# 3_-LEDBoard.net
KiCad netlist of a schematic drawn in Altium Designer
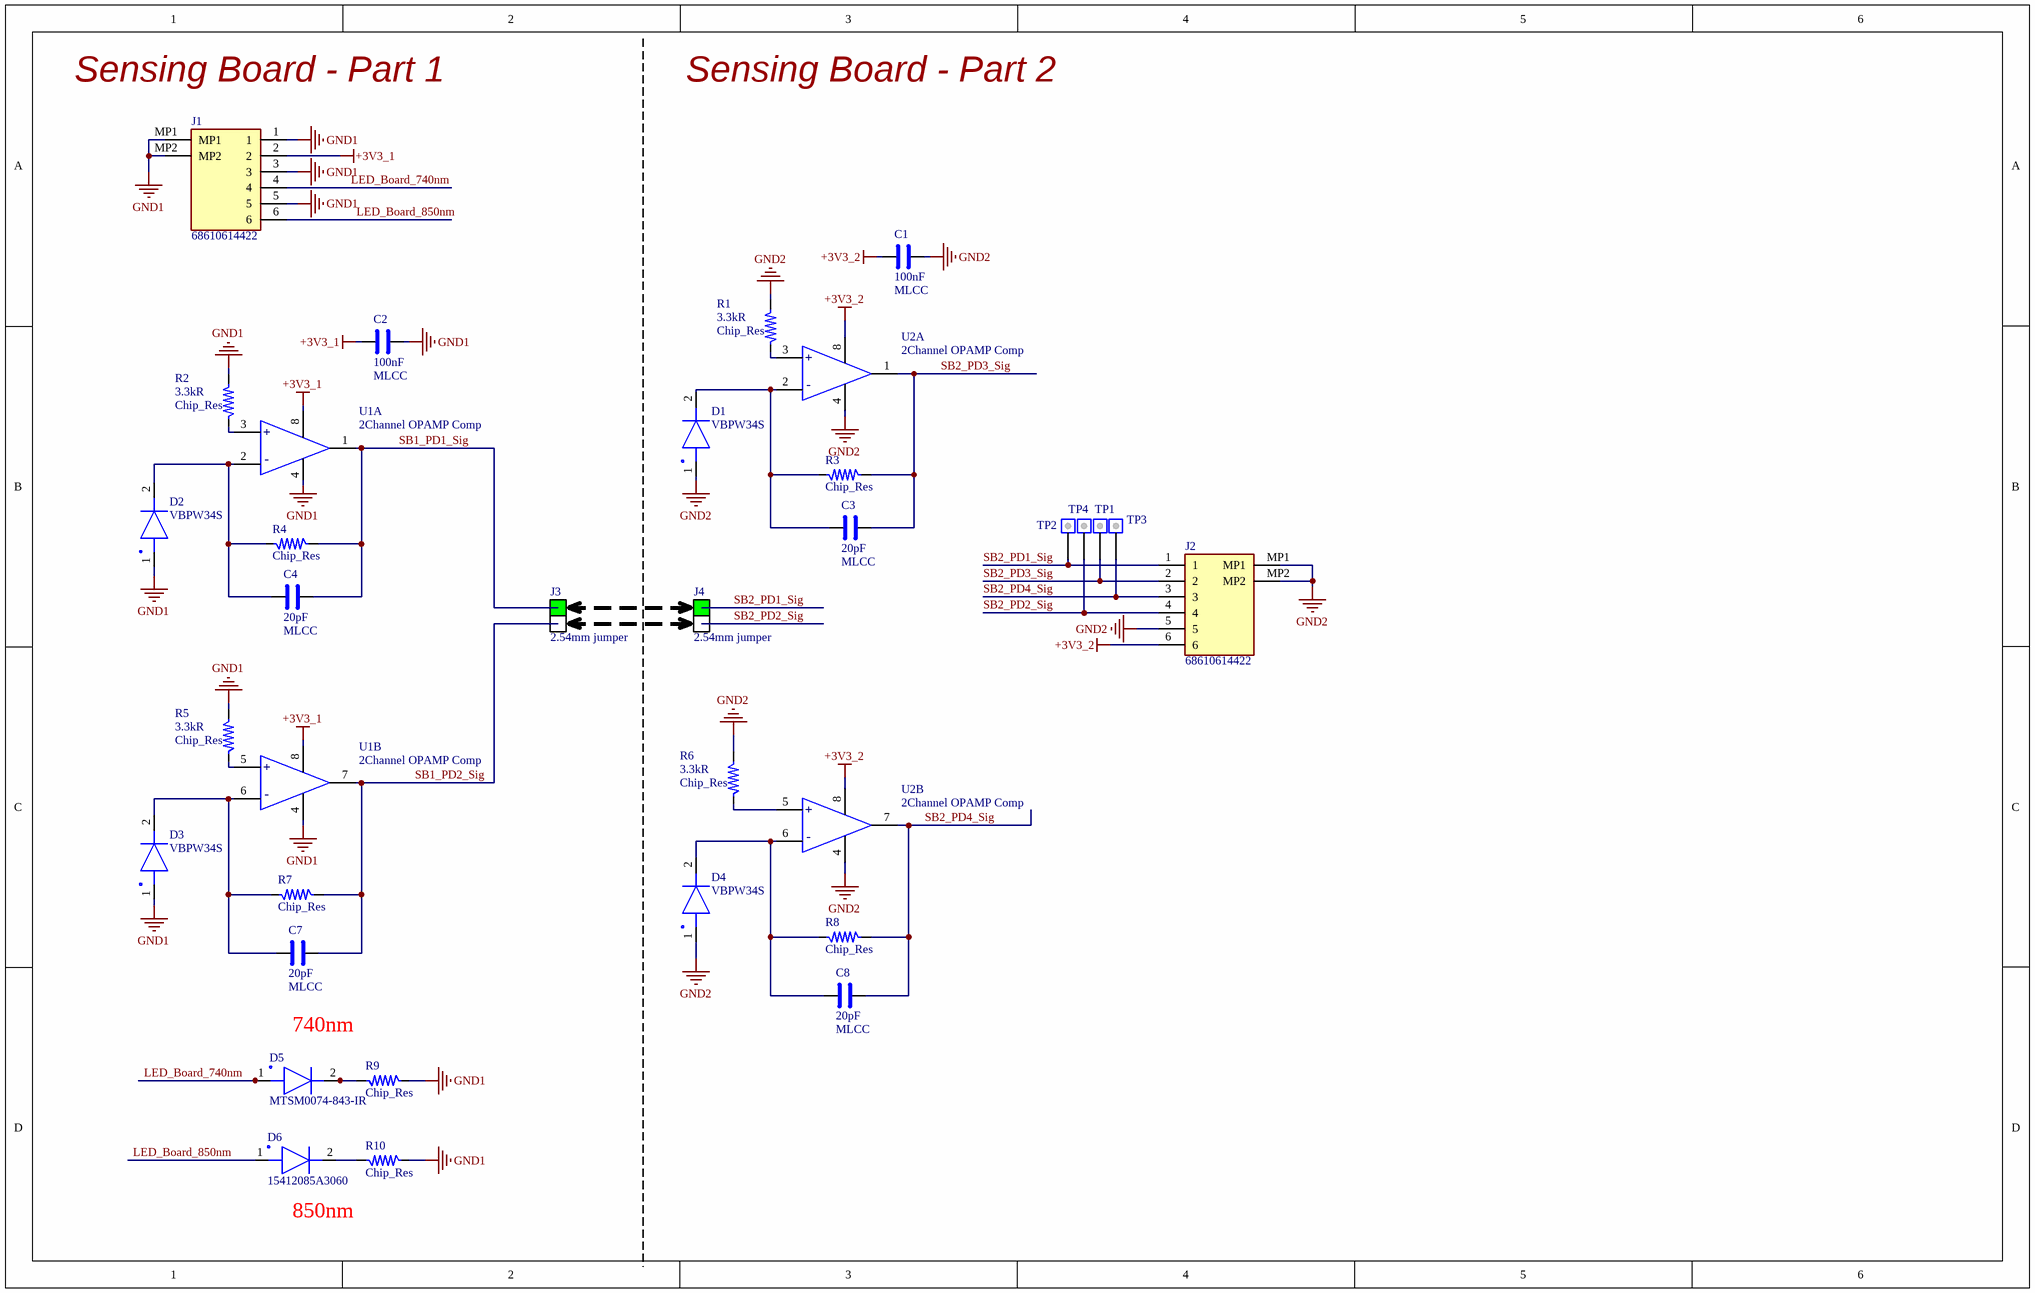
[diagram p0: [3]-LEDBoard.SchDoc]

(export (version "E")
  (design (tool "Eeschema 10.0.6"))
  (components
    (comp (ref "C1")
      (value "MLCC")
      (footprint "CAPC1005X06L")
      (description "Multilayer Ceramic Capacitor, 0.1 uF, 25 V, ± 10%, X7R, 0402 [1005 Metric]")
      (fields
        (field (name "PART NUMBER") "CC0402KRX7R8BB104")
        (field (name "ALTIUM_VALUE") "100nF")
        (field (name "MANUFACTURER") "Yageo")
      )
      (libsource (lib "Capacitors") (part "MLCC"))
    )
    (comp (ref "C2")
      (value "MLCC")
      (footprint "CAPC1005X06L")
      (description "Multilayer Ceramic Capacitor, 0.1 uF, 25 V, ± 10%, X7R, 0402 [1005 Metric]")
      (fields
        (field (name "PART NUMBER") "CC0402KRX7R8BB104")
        (field (name "ALTIUM_VALUE") "100nF")
        (field (name "MANUFACTURER") "Yageo")
      )
      (libsource (lib "Capacitors") (part "MLCC"))
    )
    (comp (ref "C3")
      (value "MLCC")
      (footprint "CAPC1608X09M")
      (description "Multilayer Ceramic Capacitor, 20 pF, 50 V, ± 5%, C0G (NP0), 0603 [1608 Metric]")
      (fields
        (field (name "PART NUMBER") "CC0603JRNPO9BN200")
        (field (name "ALTIUM_VALUE") "20pF")
        (field (name "MANUFACTURER") "Yageo")
      )
      (libsource (lib "Capacitors") (part "MLCC"))
    )
    (comp (ref "C4")
      (value "MLCC")
      (footprint "CAPC1608X09M")
      (description "Multilayer Ceramic Capacitor, 20 pF, 50 V, ± 5%, C0G (NP0), 0603 [1608 Metric]")
      (fields
        (field (name "PART NUMBER") "CC0603JRNPO9BN200")
        (field (name "ALTIUM_VALUE") "20pF")
        (field (name "MANUFACTURER") "Yageo")
      )
      (libsource (lib "Capacitors") (part "MLCC"))
    )
    (comp (ref "C7")
      (value "MLCC")
      (footprint "CAPC1608X09M")
      (description "Multilayer Ceramic Capacitor, 20 pF, 50 V, ± 5%, C0G (NP0), 0603 [1608 Metric]")
      (fields
        (field (name "PART NUMBER") "CC0603JRNPO9BN200")
        (field (name "ALTIUM_VALUE") "20pF")
        (field (name "MANUFACTURER") "Yageo")
      )
      (libsource (lib "Capacitors") (part "MLCC"))
    )
    (comp (ref "C8")
      (value "MLCC")
      (footprint "CAPC1608X09M")
      (description "Multilayer Ceramic Capacitor, 20 pF, 50 V, ± 5%, C0G (NP0), 0603 [1608 Metric]")
      (fields
        (field (name "PART NUMBER") "CC0603JRNPO9BN200")
        (field (name "ALTIUM_VALUE") "20pF")
        (field (name "MANUFACTURER") "Yageo")
      )
      (libsource (lib "Capacitors") (part "MLCC"))
    )
    (comp (ref "D1")
      (value "VBPW34S")
      (footprint "VBPW34S")
      (description "Photodiode 940nm 100ns 130° 2-SMD, Gull Wing")
      (fields (field (name "MANUFACTURER") "Vishay"))
      (libsource (lib "Optic") (part "VBPW34S"))
    )
    (comp (ref "D2")
      (value "VBPW34S")
      (footprint "VBPW34S")
      (description "Photodiode 940nm 100ns 130° 2-SMD, Gull Wing")
      (fields (field (name "MANUFACTURER") "Vishay"))
      (libsource (lib "Optic") (part "VBPW34S"))
    )
    (comp (ref "D3")
      (value "VBPW34S")
      (footprint "VBPW34S")
      (description "Photodiode 940nm 100ns 130° 2-SMD, Gull Wing")
      (fields (field (name "MANUFACTURER") "Vishay"))
      (libsource (lib "Optic") (part "VBPW34S"))
    )
    (comp (ref "D4")
      (value "VBPW34S")
      (footprint "VBPW34S")
      (description "Photodiode 940nm 100ns 130° 2-SMD, Gull Wing")
      (fields (field (name "MANUFACTURER") "Vishay"))
      (libsource (lib "Optic") (part "VBPW34S"))
    )
    (comp (ref "D5")
      (value "MTSM0074-843-IR")
      (footprint "MTSM0074-843-IR")
      (description "Infrared (IR) Emitter 740nm 1.7V 30mA 3.2mW/sr @ 30mA 1206 (3216 Metric)")
      (fields (field (name "MANUFACTURER") "Marktech Optoelectronics"))
      (libsource (lib "Optic") (part "MTSM0074-843-IR"))
    )
    (comp (ref "D6")
      (value "15412085A3060")
      (footprint "15412085A3060")
      (description "Infrared (IR) Emitter 850nm 1.4V 15mW/sr @ 20mA 30° 1206 (3216 Metric)")
      (fields (field (name "MANUFACTURER") "Wurth Elektronik"))
      (libsource (lib "Optic") (part "15412085A3060"))
    )
    (comp (ref "J1")
      (value "68610614422")
      (footprint "68610614422")
      (description "6 Position FPC Connector Contacts, Bottom 0.039\" (1.00mm) Surface Mount, Right Angle")
      (fields (field (name "MANUFACTURER") "Würth Elektronik"))
      (libsource (lib "Connector") (part "68610614422"))
    )
    (comp (ref "J2")
      (value "68610614422")
      (footprint "68610614422")
      (description "6 Position FPC Connector Contacts, Bottom 0.039\" (1.00mm) Surface Mount, Right Angle")
      (fields (field (name "MANUFACTURER") "Würth Elektronik"))
      (libsource (lib "") (part "68610614422_1"))
    )
    (comp (ref "J3")
      (value "2.54mm jumper")
      (footprint "FP_Jumper_2x2_54mm")
      (description "2x2.54mm conventional header as jumper")
      (fields (field (name "PART NUMBER") "Header2x1"))
      (libsource (lib "Connector") (part "Header2x1"))
    )
    (comp (ref "J4")
      (value "2.54mm jumper")
      (footprint "FP_Jumper_2x2_54mm")
      (description "2x2.54mm conventional header as jumper")
      (fields (field (name "PART NUMBER") "Header2x1"))
      (libsource (lib "Connector") (part "Header2x1"))
    )
    (comp (ref "R1")
      (value "Chip_Res")
      (footprint "RESC1005X04M")
      (description "SMD Chip Resistor, 3.3 kOhm, ± 5%, 63 mW, 0402 [1005 Metric], Thick Film, General Purpose")
      (fields
        (field (name "PART NUMBER") "RC0402JR-073K3L")
        (field (name "ALTIUM_VALUE") "3.3kR")
        (field (name "MANUFACTURER") "Yageo")
      )
      (libsource (lib "Resistors") (part "Chip_Res"))
    )
    (comp (ref "R2")
      (value "Chip_Res")
      (footprint "RESC1005X04M")
      (description "SMD Chip Resistor, 3.3 kOhm, ± 5%, 63 mW, 0402 [1005 Metric], Thick Film, General Purpose")
      (fields
        (field (name "PART NUMBER") "RC0402JR-073K3L")
        (field (name "ALTIUM_VALUE") "3.3kR")
        (field (name "MANUFACTURER") "Yageo")
      )
      (libsource (lib "Resistors") (part "Chip_Res"))
    )
    (comp (ref "R3")
      (value "Chip_Res")
      (footprint "RESC1608X06M")
      (description "Res Thick Film 0603 887 Ohm 1% 1/10W ±100ppm/°C Molded SMD SMD Paper T/R")
      (fields (field (name "PART NUMBER") "RC0603FR-07887RL") (field (name "MANUFACTURER") "Yageo"))
      (libsource (lib "Resistors") (part "Chip_Res"))
    )
    (comp (ref "R4")
      (value "Chip_Res")
      (footprint "RESC1608X06M")
      (description "Res Thick Film 0603 887 Ohm 1% 1/10W ±100ppm/°C Molded SMD SMD Paper T/R")
      (fields (field (name "PART NUMBER") "RC0603FR-07887RL") (field (name "MANUFACTURER") "Yageo"))
      (libsource (lib "Resistors") (part "Chip_Res"))
    )
    (comp (ref "R5")
      (value "Chip_Res")
      (footprint "RESC1005X04M")
      (description "SMD Chip Resistor, 3.3 kOhm, ± 5%, 63 mW, 0402 [1005 Metric], Thick Film, General Purpose")
      (fields
        (field (name "PART NUMBER") "RC0402JR-073K3L")
        (field (name "ALTIUM_VALUE") "3.3kR")
        (field (name "MANUFACTURER") "Yageo")
      )
      (libsource (lib "Resistors") (part "Chip_Res"))
    )
    (comp (ref "R6")
      (value "Chip_Res")
      (footprint "RESC1005X04M")
      (description "SMD Chip Resistor, 3.3 kOhm, ± 5%, 63 mW, 0402 [1005 Metric], Thick Film, General Purpose")
      (fields
        (field (name "PART NUMBER") "RC0402JR-073K3L")
        (field (name "ALTIUM_VALUE") "3.3kR")
        (field (name "MANUFACTURER") "Yageo")
      )
      (libsource (lib "Resistors") (part "Chip_Res"))
    )
    (comp (ref "R7")
      (value "Chip_Res")
      (footprint "RESC1608X06M")
      (description "Res Thick Film 0603 887 Ohm 1% 1/10W ±100ppm/°C Molded SMD SMD Paper T/R")
      (fields (field (name "PART NUMBER") "RC0603FR-07887RL") (field (name "MANUFACTURER") "Yageo"))
      (libsource (lib "Resistors") (part "Chip_Res"))
    )
    (comp (ref "R8")
      (value "Chip_Res")
      (footprint "RESC1608X06M")
      (description "Res Thick Film 0603 887 Ohm 1% 1/10W ±100ppm/°C Molded SMD SMD Paper T/R")
      (fields (field (name "PART NUMBER") "RC0603FR-07887RL") (field (name "MANUFACTURER") "Yageo"))
      (libsource (lib "Resistors") (part "Chip_Res"))
    )
    (comp (ref "R9")
      (value "Chip_Res")
      (footprint "RESC1608X06M")
      (description "SMD Chip Resistor, 33 kOhm, ± 1%, 100 mW, 0603 [1608 Metric], Thick Film, General Purpose")
      (fields (field (name "PART NUMBER") "AC0603FR-1333KL") (field (name "MANUFACTURER") "Yageo"))
      (libsource (lib "Resistors") (part "Chip_Res"))
    )
    (comp (ref "R10")
      (value "Chip_Res")
      (footprint "RESC1608X06M")
      (description "SMD Chip Resistor, 33 kOhm, ± 1%, 100 mW, 0603 [1608 Metric], Thick Film, General Purpose")
      (fields (field (name "PART NUMBER") "AC0603FR-1333KL") (field (name "MANUFACTURER") "Yageo"))
      (libsource (lib "Resistors") (part "Chip_Res"))
    )
    (comp (ref "TP1")
      (value "TP")
      (footprint "FP-TP_SMD_Narrow")
      (description "A simple test point")
      (fields (field (name "PART NUMBER") "Test Point"))
      (libsource (lib "Miscellaneous") (part "TP"))
    )
    (comp (ref "TP2")
      (value "TP")
      (footprint "FP-TP_SMD_Narrow")
      (description "A simple test point")
      (fields (field (name "PART NUMBER") "Test Point"))
      (libsource (lib "Miscellaneous") (part "TP"))
    )
    (comp (ref "TP3")
      (value "TP")
      (footprint "FP-TP_SMD_Narrow")
      (description "A simple test point")
      (fields (field (name "PART NUMBER") "Test Point"))
      (libsource (lib "Miscellaneous") (part "TP"))
    )
    (comp (ref "TP4")
      (value "TP")
      (footprint "FP-TP_SMD_Narrow")
      (description "A simple test point")
      (fields (field (name "PART NUMBER") "Test Point"))
      (libsource (lib "Miscellaneous") (part "TP"))
    )
    (comp (ref "U1")
      (value "2Channel OPAMP Comp")
      (footprint "TSOP65P490X110-8L")
      (fields (field (name "PART NUMBER") "OPA2380AIDGKR") (field (name "MANUFACTURER") "Texas Instruments"))
      (libsource (lib "ICs") (part "2Channel OPAMP Comp"))
    )
    (comp (ref "U2")
      (value "2Channel OPAMP Comp")
      (footprint "TSOP65P490X110-8L")
      (fields (field (name "PART NUMBER") "OPA2380AIDGKR") (field (name "MANUFACTURER") "Texas Instruments"))
      (libsource (lib "ICs") (part "2Channel OPAMP Comp"))
    )
  )
  (nets
    (net (code "1") (name "+3V3_1") (class "Default")
      (node (ref "C2") (pin "1") (pinfunction "1_1") (pintype "passive"))
      (node (ref "J1") (pin "2") (pinfunction "2_2") (pintype "passive"))
      (node (ref "U1") (pin "8") (pinfunction "VCC_8") (pintype "power_in"))
    )
    (net (code "2") (name "+3V3_2") (class "Default")
      (node (ref "C1") (pin "1") (pinfunction "1_1") (pintype "passive"))
      (node (ref "J2") (pin "6") (pinfunction "6_6") (pintype "passive"))
      (node (ref "U2") (pin "8") (pinfunction "VCC_8") (pintype "power_in"))
    )
    (net (code "3") (name "/LED_Board_740nm") (class "Default")
      (node (ref "D5") (pin "1") (pinfunction "Anode_1") (pintype "passive"))
      (node (ref "J1") (pin "4") (pinfunction "4_4") (pintype "passive"))
    )
    (net (code "4") (name "/LED_Board_850nm") (class "Default")
      (node (ref "D6") (pin "1") (pinfunction "Anode_1") (pintype "passive"))
      (node (ref "J1") (pin "6") (pinfunction "6_6") (pintype "passive"))
    )
    (net (code "5") (name "/SB1_PD1_Sig") (class "Default")
      (node (ref "C4") (pin "2") (pinfunction "2_2") (pintype "passive"))
      (node (ref "J3") (pin "1") (pinfunction "1_1") (pintype "passive"))
      (node (ref "R4") (pin "1") (pinfunction "1_1") (pintype "passive"))
      (node (ref "U1") (pin "1") (pinfunction "1OUT_1") (pintype "passive"))
    )
    (net (code "6") (name "/SB1_PD2_Sig") (class "Default")
      (node (ref "C7") (pin "2") (pinfunction "2_2") (pintype "passive"))
      (node (ref "J3") (pin "2") (pinfunction "2_2") (pintype "passive"))
      (node (ref "R7") (pin "1") (pinfunction "1_1") (pintype "passive"))
      (node (ref "U1") (pin "7") (pinfunction "2OUT_7") (pintype "passive"))
    )
    (net (code "7") (name "/SB2_PD1_Sig") (class "Default")
      (node (ref "J2") (pin "1") (pinfunction "1_1") (pintype "passive"))
      (node (ref "J4") (pin "1") (pinfunction "1_1") (pintype "passive"))
      (node (ref "TP2") (pin "NODE") (pinfunction "NODE_NODE") (pintype "passive"))
    )
    (net (code "8") (name "/SB2_PD2_Sig") (class "Default")
      (node (ref "J2") (pin "4") (pinfunction "4_4") (pintype "passive"))
      (node (ref "J4") (pin "2") (pinfunction "2_2") (pintype "passive"))
      (node (ref "TP4") (pin "NODE") (pinfunction "NODE_NODE") (pintype "passive"))
    )
    (net (code "9") (name "/SB2_PD3_Sig") (class "Default")
      (node (ref "C3") (pin "2") (pinfunction "2_2") (pintype "passive"))
      (node (ref "J2") (pin "2") (pinfunction "2_2") (pintype "passive"))
      (node (ref "R3") (pin "1") (pinfunction "1_1") (pintype "passive"))
      (node (ref "TP1") (pin "NODE") (pinfunction "NODE_NODE") (pintype "passive"))
      (node (ref "U2") (pin "1") (pinfunction "1OUT_1") (pintype "passive"))
    )
    (net (code "10") (name "/SB2_PD4_Sig") (class "Default")
      (node (ref "C8") (pin "2") (pinfunction "2_2") (pintype "passive"))
      (node (ref "J2") (pin "3") (pinfunction "3_3") (pintype "passive"))
      (node (ref "R8") (pin "1") (pinfunction "1_1") (pintype "passive"))
      (node (ref "TP3") (pin "NODE") (pinfunction "NODE_NODE") (pintype "passive"))
      (node (ref "U2") (pin "7") (pinfunction "2OUT_7") (pintype "passive"))
    )
    (net (code "11") (name "GND1") (class "Default")
      (node (ref "C2") (pin "2") (pinfunction "2_2") (pintype "passive"))
      (node (ref "D2") (pin "1") (pinfunction "Anode_1") (pintype "passive"))
      (node (ref "D3") (pin "1") (pinfunction "Anode_1") (pintype "passive"))
      (node (ref "J1") (pin "1") (pinfunction "1_1") (pintype "passive"))
      (node (ref "J1") (pin "3") (pinfunction "3_3") (pintype "passive"))
      (node (ref "J1") (pin "5") (pinfunction "5_5") (pintype "passive"))
      (node (ref "J1") (pin "MP1") (pinfunction "MP1_MP1") (pintype "passive"))
      (node (ref "J1") (pin "MP2") (pinfunction "MP2_MP2") (pintype "passive"))
      (node (ref "R10") (pin "2") (pinfunction "2_2") (pintype "passive"))
      (node (ref "R2") (pin "1") (pinfunction "1_1") (pintype "passive"))
      (node (ref "R5") (pin "1") (pinfunction "1_1") (pintype "passive"))
      (node (ref "R9") (pin "2") (pinfunction "2_2") (pintype "passive"))
      (node (ref "U1") (pin "4") (pinfunction "GND_4") (pintype "power_in"))
    )
    (net (code "12") (name "GND2") (class "Default")
      (node (ref "C1") (pin "2") (pinfunction "2_2") (pintype "passive"))
      (node (ref "D1") (pin "1") (pinfunction "Anode_1") (pintype "passive"))
      (node (ref "D4") (pin "1") (pinfunction "Anode_1") (pintype "passive"))
      (node (ref "J2") (pin "5") (pinfunction "5_5") (pintype "passive"))
      (node (ref "J2") (pin "MP1") (pinfunction "MP1_MP1") (pintype "passive"))
      (node (ref "J2") (pin "MP2") (pinfunction "MP2_MP2") (pintype "passive"))
      (node (ref "R1") (pin "1") (pinfunction "1_1") (pintype "passive"))
      (node (ref "R6") (pin "1") (pinfunction "1_1") (pintype "passive"))
      (node (ref "U2") (pin "4") (pinfunction "GND_4") (pintype "power_in"))
    )
    (net (code "13") (name "Net-(D1-Cathode)") (class "Default")
      (node (ref "C3") (pin "1") (pinfunction "1_1") (pintype "passive"))
      (node (ref "D1") (pin "2") (pinfunction "Cathode_2") (pintype "passive"))
      (node (ref "R3") (pin "2") (pinfunction "2_2") (pintype "passive"))
      (node (ref "U2") (pin "2") (pinfunction "1IN-_2") (pintype "passive"))
    )
    (net (code "14") (name "Net-(D2-Cathode)") (class "Default")
      (node (ref "C4") (pin "1") (pinfunction "1_1") (pintype "passive"))
      (node (ref "D2") (pin "2") (pinfunction "Cathode_2") (pintype "passive"))
      (node (ref "R4") (pin "2") (pinfunction "2_2") (pintype "passive"))
      (node (ref "U1") (pin "2") (pinfunction "1IN-_2") (pintype "passive"))
    )
    (net (code "15") (name "Net-(D3-Cathode)") (class "Default")
      (node (ref "C7") (pin "1") (pinfunction "1_1") (pintype "passive"))
      (node (ref "D3") (pin "2") (pinfunction "Cathode_2") (pintype "passive"))
      (node (ref "R7") (pin "2") (pinfunction "2_2") (pintype "passive"))
      (node (ref "U1") (pin "6") (pinfunction "2IN-_6") (pintype "passive"))
    )
    (net (code "16") (name "Net-(D4-Cathode)") (class "Default")
      (node (ref "C8") (pin "1") (pinfunction "1_1") (pintype "passive"))
      (node (ref "D4") (pin "2") (pinfunction "Cathode_2") (pintype "passive"))
      (node (ref "R8") (pin "2") (pinfunction "2_2") (pintype "passive"))
      (node (ref "U2") (pin "6") (pinfunction "2IN-_6") (pintype "passive"))
    )
    (net (code "17") (name "Net-(D5-Cathode)") (class "Default")
      (node (ref "D5") (pin "2") (pinfunction "Cathode_2") (pintype "passive"))
      (node (ref "R9") (pin "1") (pinfunction "1_1") (pintype "passive"))
    )
    (net (code "18") (name "Net-(D6-Cathode)") (class "Default")
      (node (ref "D6") (pin "2") (pinfunction "Cathode_2") (pintype "passive"))
      (node (ref "R10") (pin "1") (pinfunction "1_1") (pintype "passive"))
    )
    (net (code "19") (name "Net-(U1A-1IN+)") (class "Default")
      (node (ref "R2") (pin "2") (pinfunction "2_2") (pintype "passive"))
      (node (ref "U1") (pin "3") (pinfunction "1IN+_3") (pintype "passive"))
    )
    (net (code "20") (name "Net-(U1B-2IN+)") (class "Default")
      (node (ref "R5") (pin "2") (pinfunction "2_2") (pintype "passive"))
      (node (ref "U1") (pin "5") (pinfunction "2IN+_5") (pintype "passive"))
    )
    (net (code "21") (name "Net-(U2A-1IN+)") (class "Default")
      (node (ref "R1") (pin "2") (pinfunction "2_2") (pintype "passive"))
      (node (ref "U2") (pin "3") (pinfunction "1IN+_3") (pintype "passive"))
    )
    (net (code "22") (name "Net-(U2B-2IN+)") (class "Default")
      (node (ref "R6") (pin "2") (pinfunction "2_2") (pintype "passive"))
      (node (ref "U2") (pin "5") (pinfunction "2IN+_5") (pintype "passive"))
    )
  )
)
